# madiz_plate_sheet_v3_2.net
KiCad netlist of a schematic drawn in EasyEDA
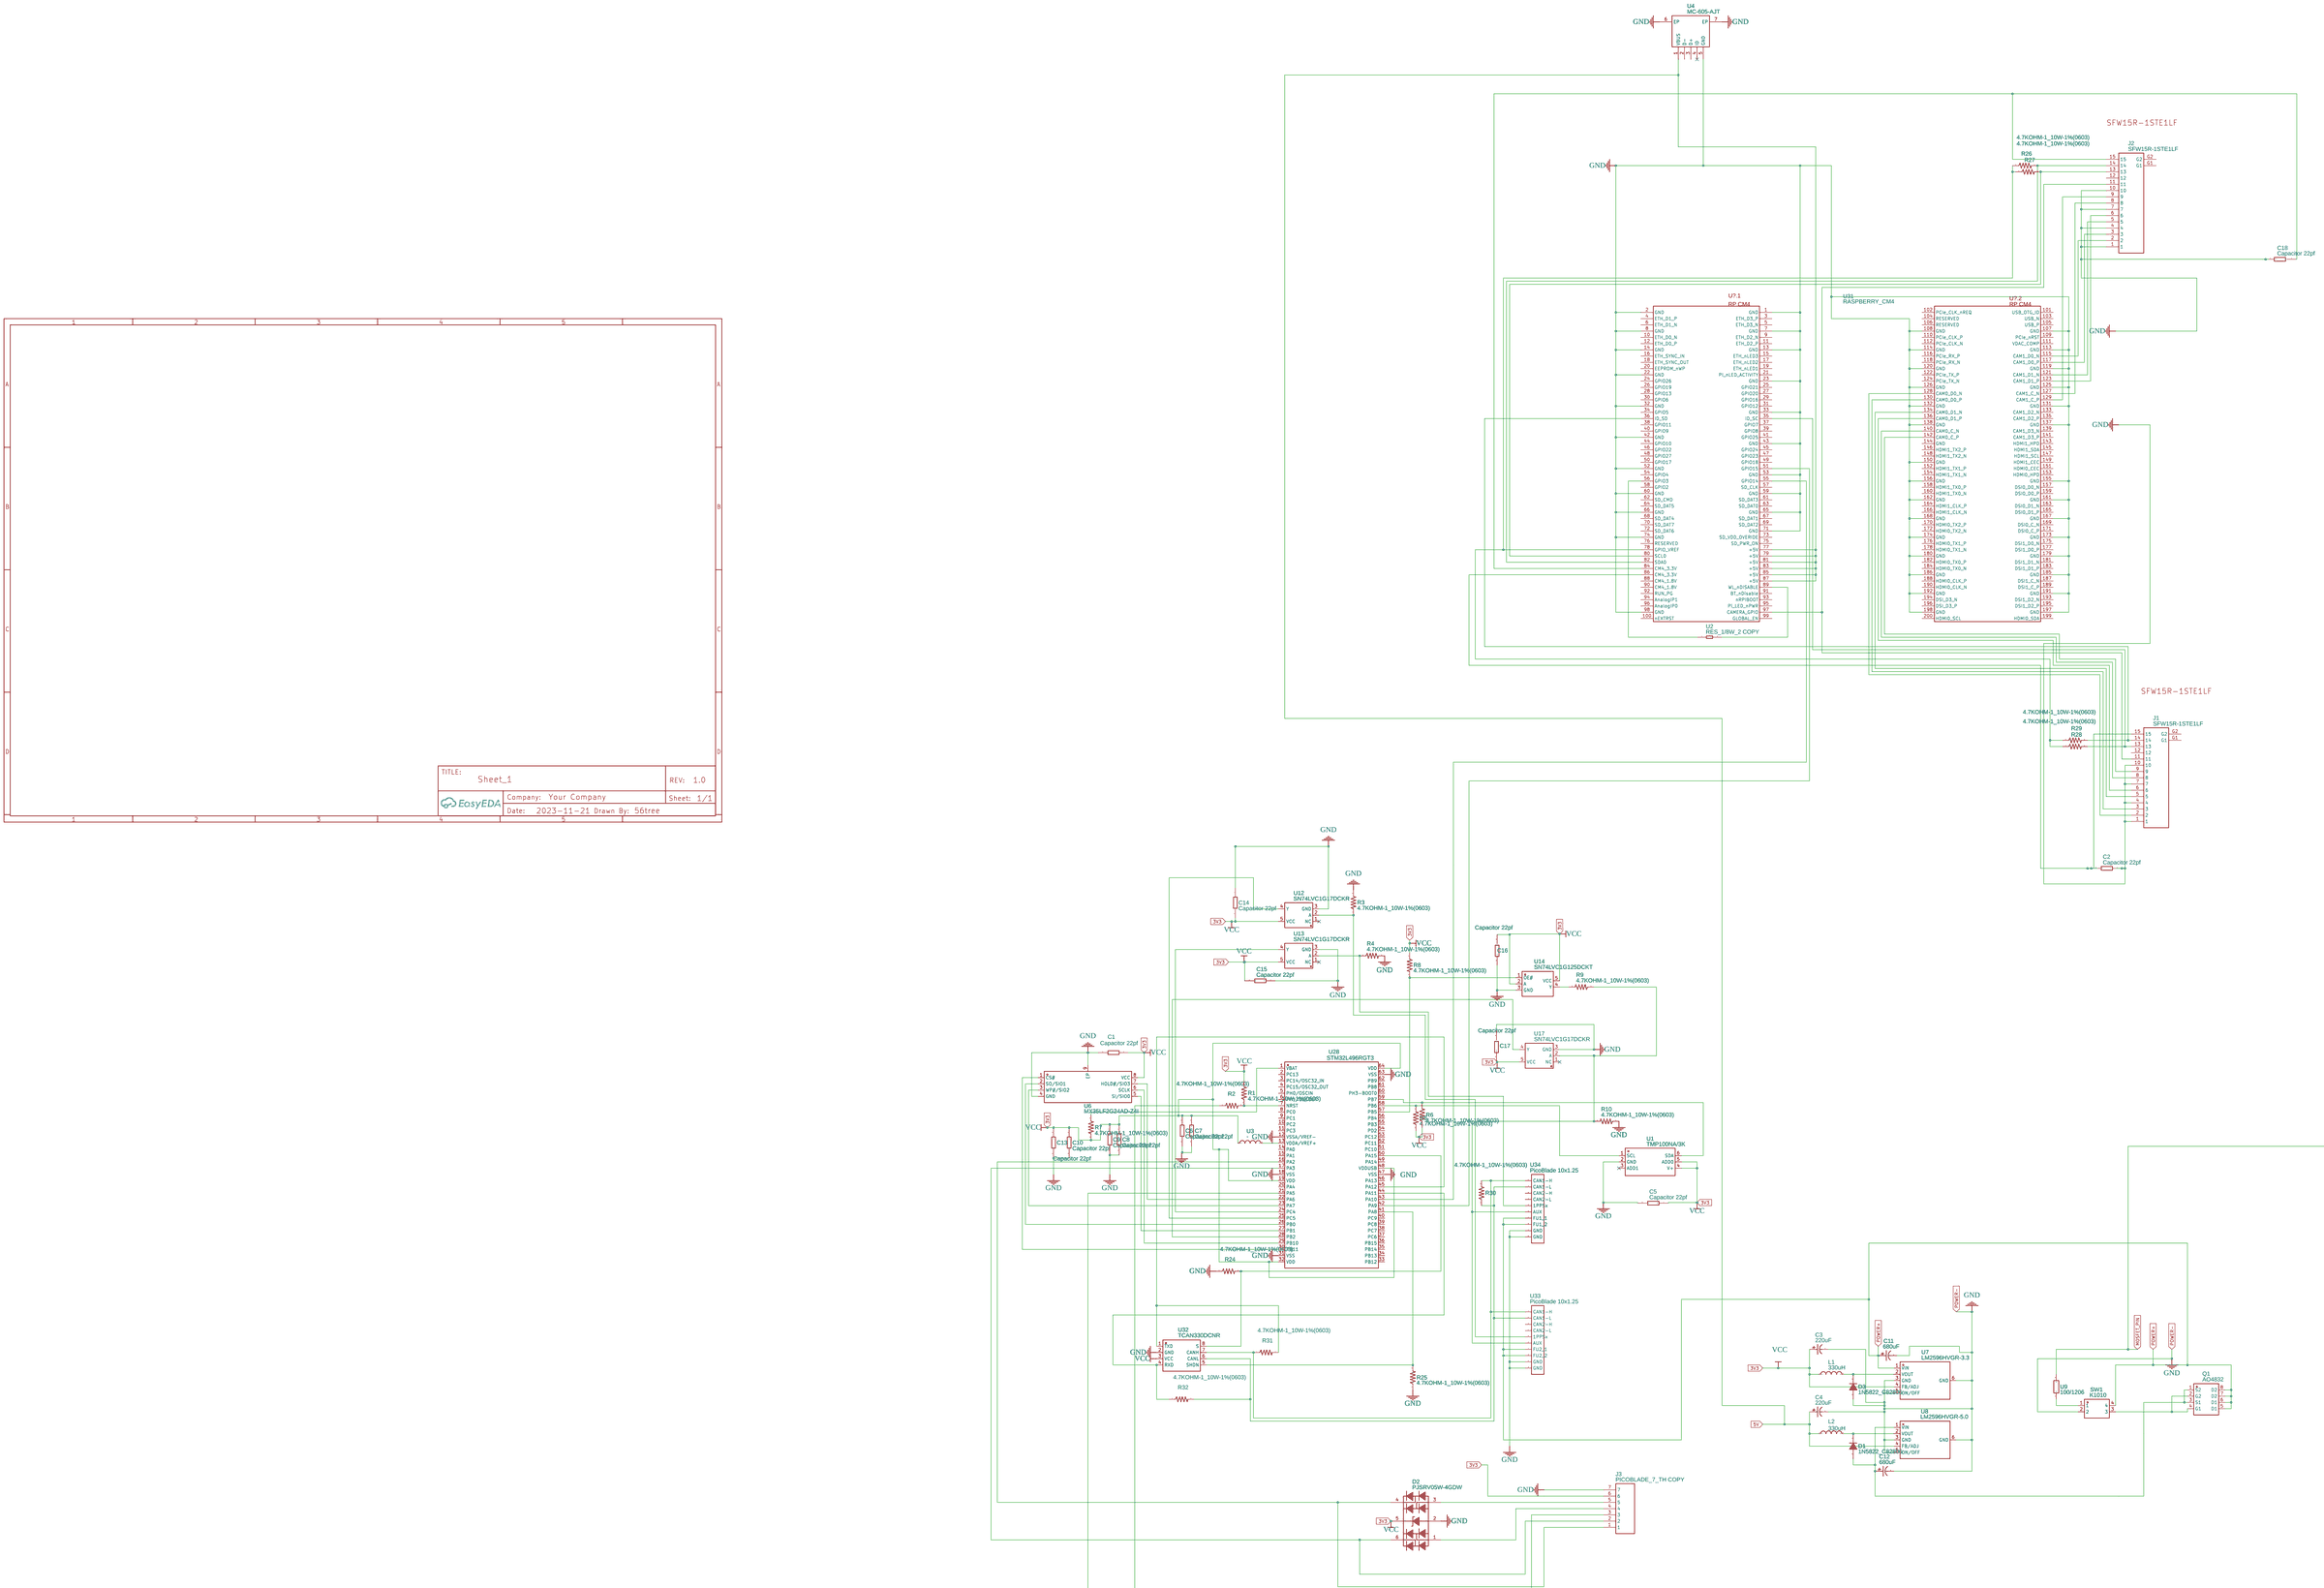
[diagram p0: schematic sheet]

(export (version "E")
  (design (tool "Eeschema 10.0.6"))
  (components
    (comp (ref "C1")
      (value "Capacitor 22pf")
      (fields (field (name "Manufacturer Part") "C0805C220J5GACTU") (field (name "Manufacturer") "KEMET"))
      (libsource (lib "") (part "Capacitor 22pf_1"))
    )
    (comp (ref "C2")
      (value "Capacitor 22pf")
      (fields (field (name "Manufacturer Part") "C0805C220J5GACTU") (field (name "Manufacturer") "KEMET"))
      (libsource (lib "") (part "Capacitor 22pf_1"))
    )
    (comp (ref "C3")
      (value "220uF")
      (fields
        (field (name "Manufacturer Part") "KS227M016F07RR0VH2FP0")
        (field (name "Manufacturer") "CX(承兴)")
      )
      (libsource (lib "") (part "220uF 16V 8*7"))
    )
    (comp (ref "C4")
      (value "220uF")
      (fields
        (field (name "Manufacturer Part") "KS227M016F07RR0VH2FP0")
        (field (name "Manufacturer") "CX(承兴)")
      )
      (libsource (lib "") (part "220uF 16V 8*7"))
    )
    (comp (ref "C5")
      (value "Capacitor 22pf")
      (fields (field (name "Manufacturer Part") "C0805C220J5GACTU") (field (name "Manufacturer") "KEMET"))
      (libsource (lib "") (part "Capacitor 22pf_1"))
    )
    (comp (ref "C6")
      (value "Capacitor 22pf")
      (fields (field (name "Manufacturer Part") "C0805C220J5GACTU") (field (name "Manufacturer") "KEMET"))
      (libsource (lib "") (part "Capacitor 22pf"))
    )
    (comp (ref "C7")
      (value "Capacitor 22pf")
      (fields (field (name "Manufacturer Part") "C0805C220J5GACTU") (field (name "Manufacturer") "KEMET"))
      (libsource (lib "") (part "Capacitor 22pf"))
    )
    (comp (ref "C8")
      (value "Capacitor 22pf")
      (fields (field (name "Manufacturer Part") "C0805C220J5GACTU") (field (name "Manufacturer") "KEMET"))
      (libsource (lib "") (part "Capacitor 22pf"))
    )
    (comp (ref "C9")
      (value "Capacitor 22pf")
      (fields (field (name "Manufacturer Part") "C0805C220J5GACTU") (field (name "Manufacturer") "KEMET"))
      (libsource (lib "") (part "Capacitor 22pf"))
    )
    (comp (ref "C10")
      (value "Capacitor 22pf")
      (fields (field (name "Manufacturer Part") "C0805C220J5GACTU") (field (name "Manufacturer") "KEMET"))
      (libsource (lib "") (part "Capacitor 22pf"))
    )
    (comp (ref "C11")
      (value "680uF")
      (fields
        (field (name "Manufacturer Part") "GR687M016F16RR0VL4FP0")
        (field (name "Manufacturer") "CX(承兴)")
      )
      (libsource (lib "") (part "680uF 16V 8*16"))
    )
    (comp (ref "C12")
      (value "680uF")
      (fields
        (field (name "Manufacturer Part") "GR687M016F16RR0VL4FP0")
        (field (name "Manufacturer") "CX(承兴)")
      )
      (libsource (lib "") (part "680uF 16V 8*16"))
    )
    (comp (ref "C13")
      (value "Capacitor 22pf")
      (fields (field (name "Manufacturer Part") "C0805C220J5GACTU") (field (name "Manufacturer") "KEMET"))
      (libsource (lib "") (part "Capacitor 22pf"))
    )
    (comp (ref "C14")
      (value "Capacitor 22pf")
      (fields (field (name "Manufacturer Part") "C0805C220J5GACTU") (field (name "Manufacturer") "KEMET"))
      (libsource (lib "") (part "Capacitor 22pf"))
    )
    (comp (ref "C15")
      (value "Capacitor 22pf")
      (fields (field (name "Manufacturer Part") "C0805C220J5GACTU") (field (name "Manufacturer") "KEMET"))
      (libsource (lib "") (part "Capacitor 22pf_1"))
    )
    (comp (ref "C16")
      (value "Capacitor 22pf")
      (fields (field (name "Manufacturer Part") "C0805C220J5GACTU") (field (name "Manufacturer") "KEMET"))
      (libsource (lib "") (part "Capacitor 22pf_3"))
    )
    (comp (ref "C17")
      (value "Capacitor 22pf")
      (fields (field (name "Manufacturer Part") "C0805C220J5GACTU") (field (name "Manufacturer") "KEMET"))
      (libsource (lib "") (part "Capacitor 22pf_3"))
    )
    (comp (ref "C18")
      (value "Capacitor 22pf")
      (fields (field (name "Manufacturer Part") "C0805C220J5GACTU") (field (name "Manufacturer") "KEMET"))
      (libsource (lib "") (part "Capacitor 22pf_2"))
    )
    (comp (ref "D1")
      (value "1N5822_C82806")
      (fields (field (name "Manufacturer Part") "1N5822") (field (name "Manufacturer") "LRC(乐山无线电)"))
      (libsource (lib "") (part "1N5822_C82806"))
    )
    (comp (ref "D2")
      (value "PJSRV05W-4GDW")
      (fields
        (field (name "Manufacturer Part") "PJSRV05W-4GDW_R1_00001")
        (field (name "Manufacturer") "PANJIT(强茂)")
      )
      (libsource (lib "") (part "PJSRV05W-4GDW"))
    )
    (comp (ref "D3")
      (value "1N5822_C82806")
      (fields (field (name "Manufacturer Part") "1N5822") (field (name "Manufacturer") "LRC(乐山无线电)"))
      (libsource (lib "") (part "1N5822_C82806"))
    )
    (comp (ref "J1")
      (value "SFW15R-1STE1LF")
      (fields (field (name "Manufacturer") "Amphenol FCI"))
      (libsource (lib "") (part "SFW15R-1STE1LF_1"))
    )
    (comp (ref "J2")
      (value "SFW15R-1STE1LF")
      (fields (field (name "Manufacturer") "Amphenol FCI"))
      (libsource (lib "") (part "SFW15R-1STE1LF"))
    )
    (comp (ref "J3")
      (value "PICOBLADE_7_TH COPY")
      (fields (field (name "Manufacturer Part") "0530481510"))
      (libsource (lib "") (part "PICOBLADE_7_TH COPY"))
    )
    (comp (ref "L1")
      (value "330uH")
      (fields (field (name "Manufacturer Part") "B82477G4334M000") (field (name "Manufacturer") "TDK"))
      (libsource (lib "") (part "B82477G4334M000"))
    )
    (comp (ref "L2")
      (value "330uH")
      (fields (field (name "Manufacturer Part") "B82477G4334M000") (field (name "Manufacturer") "TDK"))
      (libsource (lib "") (part "B82477G4334M000"))
    )
    (comp (ref "Q1")
      (value "AO4832")
      (fields (field (name "Manufacturer") "AOS"))
      (libsource (lib "") (part "AO4832"))
    )
    (comp (ref "R1") (value "4.7KOHM-1_10W-1%(0603)") (libsource (lib "") (part "4.7KOHM-1_10W-1%(0603)_2")))
    (comp (ref "R2") (value "4.7KOHM-1_10W-1%(0603)") (libsource (lib "") (part "4.7KOHM-1_10W-1%(0603)")))
    (comp (ref "R3") (value "4.7KOHM-1_10W-1%(0603)") (libsource (lib "") (part "4.7KOHM-1_10W-1%(0603)_2")))
    (comp (ref "R4") (value "4.7KOHM-1_10W-1%(0603)") (libsource (lib "") (part "4.7KOHM-1_10W-1%(0603)")))
    (comp (ref "R5") (value "4.7KOHM-1_10W-1%(0603)") (libsource (lib "") (part "4.7KOHM-1_10W-1%(0603)_2")))
    (comp (ref "R6") (value "4.7KOHM-1_10W-1%(0603)") (libsource (lib "") (part "4.7KOHM-1_10W-1%(0603)_2")))
    (comp (ref "R7") (value "4.7KOHM-1_10W-1%(0603)") (libsource (lib "") (part "4.7KOHM-1_10W-1%(0603)_2")))
    (comp (ref "R8") (value "4.7KOHM-1_10W-1%(0603)") (libsource (lib "") (part "4.7KOHM-1_10W-1%(0603)_3")))
    (comp (ref "R9") (value "4.7KOHM-1_10W-1%(0603)") (libsource (lib "") (part "4.7KOHM-1_10W-1%(0603)_1")))
    (comp (ref "R10") (value "4.7KOHM-1_10W-1%(0603)") (libsource (lib "") (part "4.7KOHM-1_10W-1%(0603)_1")))
    (comp (ref "R24") (value "4.7KOHM-1_10W-1%(0603)") (libsource (lib "") (part "4.7KOHM-1_10W-1%(0603)")))
    (comp (ref "R25") (value "4.7KOHM-1_10W-1%(0603)") (libsource (lib "") (part "4.7KOHM-1_10W-1%(0603)_2")))
    (comp (ref "R26") (value "4.7KOHM-1_10W-1%(0603)") (libsource (lib "") (part "4.7KOHM-1_10W-1%(0603)")))
    (comp (ref "R27") (value "4.7KOHM-1_10W-1%(0603)") (libsource (lib "") (part "4.7KOHM-1_10W-1%(0603)")))
    (comp (ref "R28") (value "4.7KOHM-1_10W-1%(0603)") (libsource (lib "") (part "4.7KOHM-1_10W-1%(0603)")))
    (comp (ref "R29") (value "4.7KOHM-1_10W-1%(0603)") (libsource (lib "") (part "4.7KOHM-1_10W-1%(0603)")))
    (comp (ref "R30") (value "4.7KOHM-1_10W-1%(0603)") (libsource (lib "") (part "4.7KOHM-1_10W-1%(0603)_2")))
    (comp (ref "R31") (value "4.7KOHM-1_10W-1%(0603)") (libsource (lib "") (part "4.7KOHM-1_10W-1%(0603)")))
    (comp (ref "R32") (value "4.7KOHM-1_10W-1%(0603)") (libsource (lib "") (part "4.7KOHM-1_10W-1%(0603)")))
    (comp (ref "SW1")
      (value "K1010")
      (fields (field (name "Manufacturer") "Cosmo"))
      (libsource (lib "") (part "K1010"))
    )
    (comp (ref "U1")
      (value "TMP100NA/3K")
      (fields (field (name "Manufacturer") "TI(德州仪器)"))
      (libsource (lib "") (part "TMP100NA/3K"))
    )
    (comp (ref "U2") (value "RES_1/8W_2 COPY") (libsource (lib "") (part "RES_1/8W_2 COPY")))
    (comp (ref "U3")
      (value "-")
      (fields (field (name "Manufacturer Part") "SDR0302-151KL"))
      (libsource (lib "") (part "SDR0302-151KL"))
    )
    (comp (ref "U4")
      (value "MC-605-AJT")
      (fields (field (name "Manufacturer") "HANBO(汉博)"))
      (libsource (lib "") (part "MC-605-AJT"))
    )
    (comp (ref "U6")
      (value "MX35LF2G24AD-Z4I")
      (fields (field (name "Manufacturer") "MXIC(旺宏电子)"))
      (libsource (lib "") (part "MX35LF2G24AD-Z4I"))
    )
    (comp (ref "U7")
      (value "LM2596HVGR-3.3")
      (fields (field (name "Manufacturer Part") "LM2596HVGR-5.0") (field (name "Manufacturer") "HTC"))
      (libsource (lib "") (part "LM2596HVGR-5.0"))
    )
    (comp (ref "U8")
      (value "LM2596HVGR-5.0")
      (fields (field (name "Manufacturer") "HTC"))
      (libsource (lib "") (part "LM2596HVGR-5.0"))
    )
    (comp (ref "U9")
      (value "100/1206")
      (fields (field (name "Manufacturer Part") "1K2/1206"))
      (libsource (lib "") (part "1K2/1206"))
    )
    (comp (ref "U12")
      (value "SN74LVC1G17DCKR")
      (fields (field (name "Manufacturer") "TI(德州仪器)"))
      (libsource (lib "") (part "SN74LVC1G17DCKR"))
    )
    (comp (ref "U13")
      (value "SN74LVC1G17DCKR")
      (fields (field (name "Manufacturer") "TI(德州仪器)"))
      (libsource (lib "") (part "SN74LVC1G17DCKR"))
    )
    (comp (ref "U14")
      (value "SN74LVC1G125DCKT")
      (fields (field (name "Manufacturer") "TI(德州仪器)"))
      (libsource (lib "") (part "SN74LVC1G125DCKT"))
    )
    (comp (ref "U17")
      (value "SN74LVC1G17DCKR")
      (fields (field (name "Manufacturer") "TI(德州仪器)"))
      (libsource (lib "") (part "SN74LVC1G17DCKR"))
    )
    (comp (ref "U28")
      (value "STM32L496RGT3")
      (fields (field (name "Manufacturer") "ST(意法半导体)"))
      (libsource (lib "") (part "STM32L496RGT3"))
    )
    (comp (ref "U31") (value "RASPBERRY_CM4") (libsource (lib "") (part "RASPBERRY_CM4")))
    (comp (ref "U32")
      (value "TCAN330DCNR")
      (fields (field (name "Manufacturer") "TI(德州仪器)"))
      (libsource (lib "") (part "TCAN330DCNR"))
    )
    (comp (ref "U33")
      (value "PicoBlade 10x1.25")
      (fields (field (name "Manufacturer Part") "15134-1002") (field (name "Manufacturer") "Molex"))
      (libsource (lib "") (part "PicoBlade 10x1.25_1"))
    )
    (comp (ref "U34")
      (value "PicoBlade 10x1.25")
      (fields (field (name "Manufacturer Part") "15134-1002") (field (name "Manufacturer") "Molex"))
      (libsource (lib "") (part "PicoBlade 10x1.25"))
    )
  )
  (nets
    (net (code "1") (name "3V3") (class "Default")
      (node (ref "C1") (pin "1") (pinfunction "1_1") (pintype "unspecified"))
      (node (ref "C10") (pin "1") (pinfunction "1_1") (pintype "unspecified"))
      (node (ref "C13") (pin "1") (pinfunction "1_1") (pintype "unspecified"))
      (node (ref "C14") (pin "2") (pinfunction "2_2") (pintype "unspecified"))
      (node (ref "C15") (pin "2") (pinfunction "2_2") (pintype "unspecified"))
      (node (ref "C16") (pin "2") (pinfunction "2_2") (pintype "unspecified"))
      (node (ref "C17") (pin "1") (pinfunction "1_1") (pintype "unspecified"))
      (node (ref "C3") (pin "1") (pinfunction "1_1") (pintype "input"))
      (node (ref "C5") (pin "1") (pinfunction "1_1") (pintype "unspecified"))
      (node (ref "C6") (pin "1") (pinfunction "1_1") (pintype "unspecified"))
      (node (ref "C7") (pin "1") (pinfunction "1_1") (pintype "unspecified"))
      (node (ref "C8") (pin "1") (pinfunction "1_1") (pintype "unspecified"))
      (node (ref "C9") (pin "1") (pinfunction "1_1") (pintype "unspecified"))
      (node (ref "D2") (pin "5") (pinfunction "5_5") (pintype "unspecified"))
      (node (ref "J3") (pin "6") (pinfunction "6_6") (pintype "unspecified"))
      (node (ref "L1") (pin "1") (pinfunction "1_1") (pintype "unspecified"))
      (node (ref "R1") (pin "2") (pinfunction "2_2") (pintype "unspecified"))
      (node (ref "R5") (pin "1") (pinfunction "1_1") (pintype "unspecified"))
      (node (ref "R6") (pin "1") (pinfunction "1_1") (pintype "unspecified"))
      (node (ref "R7") (pin "1") (pinfunction "1_1") (pintype "unspecified"))
      (node (ref "R8") (pin "1") (pinfunction "1_1") (pintype "unspecified"))
      (node (ref "U1") (pin "4") (pinfunction "V+_4") (pintype "unspecified"))
      (node (ref "U1") (pin "5") (pinfunction "ADD0_5") (pintype "unspecified"))
      (node (ref "U12") (pin "5") (pinfunction "VCC_5") (pintype "unspecified"))
      (node (ref "U13") (pin "5") (pinfunction "VCC_5") (pintype "unspecified"))
      (node (ref "U14") (pin "2") (pinfunction "A_2") (pintype "unspecified"))
      (node (ref "U14") (pin "5") (pinfunction "VCC_5") (pintype "unspecified"))
      (node (ref "U17") (pin "5") (pinfunction "VCC_5") (pintype "unspecified"))
      (node (ref "U28") (pin "19") (pinfunction "VDD_19") (pintype "unspecified"))
      (node (ref "U28") (pin "32") (pinfunction "VDD_32") (pintype "unspecified"))
      (node (ref "U28") (pin "48") (pinfunction "VDDUSB_48") (pintype "unspecified"))
      (node (ref "U28") (pin "64") (pinfunction "VDD_64") (pintype "unspecified"))
      (node (ref "U3") (pin "1") (pinfunction "1_1") (pintype "unspecified"))
      (node (ref "U32") (pin "3") (pinfunction "VCC_3") (pintype "unspecified"))
      (node (ref "U6") (pin "8") (pinfunction "VCC_8") (pintype "unspecified"))
      (node (ref "U7") (pin "4") (pinfunction "FB/ADJ_4") (pintype "unspecified"))
    )
    (net (code "2") (name "5V") (class "Default")
      (node (ref "C4") (pin "1") (pinfunction "1_1") (pintype "input"))
      (node (ref "L2") (pin "1") (pinfunction "1_1") (pintype "unspecified"))
      (node (ref "U31") (pin "77") (pinfunction "+5V_77") (pintype "bidirectional"))
      (node (ref "U31") (pin "79") (pinfunction "+5V_79") (pintype "bidirectional"))
      (node (ref "U31") (pin "81") (pinfunction "+5V_81") (pintype "bidirectional"))
      (node (ref "U31") (pin "83") (pinfunction "+5V_83") (pintype "bidirectional"))
      (node (ref "U31") (pin "85") (pinfunction "+5V_85") (pintype "bidirectional"))
      (node (ref "U31") (pin "87") (pinfunction "+5V_87") (pintype "bidirectional"))
      (node (ref "U4") (pin "1") (pinfunction "VBUS_1") (pintype "unspecified"))
      (node (ref "U8") (pin "4") (pinfunction "FB/ADJ_4") (pintype "unspecified"))
    )
    (net (code "3") (name "MOSFET_PIN") (class "Default")
      (node (ref "U28") (pin "21") (pinfunction "PA5_21") (pintype "unspecified"))
      (node (ref "U9") (pin "2") (pinfunction "2_2") (pintype "unspecified"))
    )
    (net (code "4") (name "Net-(C2-Pad2)") (class "Default")
      (node (ref "C2") (pin "2") (pinfunction "2_2") (pintype "unspecified"))
      (node (ref "J1") (pin "15") (pinfunction "15_15") (pintype "unspecified"))
      (node (ref "U31") (pin "86") (pinfunction "CM4_3.3V_86") (pintype "bidirectional"))
    )
    (net (code "5") (name "Net-(C18-Pad2)") (class "Default")
      (node (ref "C18") (pin "2") (pinfunction "2_2") (pintype "unspecified"))
      (node (ref "J2") (pin "15") (pinfunction "15_15") (pintype "unspecified"))
      (node (ref "U31") (pin "84") (pinfunction "CM4_3.3V_84") (pintype "bidirectional"))
    )
    (net (code "6") (name "Net-(D1-A)") (class "Default")
      (node (ref "C12") (pin "1") (pinfunction "1_1") (pintype "input"))
      (node (ref "D1") (pin "2") (pinfunction "A_2") (pintype "unspecified"))
      (node (ref "Q1") (pin "1") (pinfunction "S2_1") (pintype "unspecified"))
      (node (ref "Q1") (pin "3") (pinfunction "S1_3") (pintype "unspecified"))
      (node (ref "U8") (pin "1") (pinfunction "VIN_1") (pintype "unspecified"))
    )
    (net (code "7") (name "Net-(D1-C)") (class "Default")
      (node (ref "D1") (pin "1") (pinfunction "C_1") (pintype "unspecified"))
      (node (ref "L2") (pin "2") (pinfunction "2_2") (pintype "unspecified"))
      (node (ref "U8") (pin "2") (pinfunction "VOUT_2") (pintype "unspecified"))
    )
    (net (code "8") (name "Net-(D2-Pad1)") (class "Default")
      (node (ref "D2") (pin "1") (pinfunction "1_1") (pintype "unspecified"))
      (node (ref "J3") (pin "4") (pinfunction "4_4") (pintype "unspecified"))
    )
    (net (code "9") (name "Net-(D2-Pad3)") (class "Default")
      (node (ref "D2") (pin "3") (pinfunction "3_3") (pintype "unspecified"))
      (node (ref "J3") (pin "5") (pinfunction "5_5") (pintype "unspecified"))
    )
    (net (code "10") (name "Net-(D3-C)") (class "Default")
      (node (ref "D3") (pin "1") (pinfunction "C_1") (pintype "unspecified"))
      (node (ref "L1") (pin "2") (pinfunction "2_2") (pintype "unspecified"))
      (node (ref "U7") (pin "2") (pinfunction "VOUT_2") (pintype "unspecified"))
    )
    (net (code "11") (name "Net-(J3-Pad3)") (class "Default")
      (node (ref "J3") (pin "3") (pinfunction "3_3") (pintype "unspecified"))
      (node (ref "R2") (pin "1") (pinfunction "1_1") (pintype "unspecified"))
    )
    (net (code "12") (name "Net-(Q1-G1)") (class "Default")
      (node (ref "Q1") (pin "2") (pinfunction "G2_2") (pintype "unspecified"))
      (node (ref "Q1") (pin "4") (pinfunction "G1_4") (pintype "unspecified"))
      (node (ref "SW1") (pin "3") (pinfunction "3_3") (pintype "unspecified"))
    )
    (net (code "13") (name "Net-(SW1-Pad1)") (class "Default")
      (node (ref "SW1") (pin "1") (pinfunction "1_1") (pintype "unspecified"))
      (node (ref "U9") (pin "1") (pinfunction "1_1") (pintype "unspecified"))
    )
    (net (code "14") (name "Net-(U1-SCL)") (class "Default")
      (node (ref "R5") (pin "2") (pinfunction "2_2") (pintype "unspecified"))
      (node (ref "U1") (pin "1") (pinfunction "SCL_1") (pintype "unspecified"))
      (node (ref "U28") (pin "58") (pinfunction "PB6_58") (pintype "unspecified"))
    )
    (net (code "15") (name "Net-(U1-SDA)") (class "Default")
      (node (ref "R6") (pin "2") (pinfunction "2_2") (pintype "unspecified"))
      (node (ref "U1") (pin "6") (pinfunction "SDA_6") (pintype "unspecified"))
      (node (ref "U28") (pin "59") (pinfunction "PB7_59") (pintype "unspecified"))
    )
    (net (code "16") (name "Net-(U12-A)") (class "Default")
      (node (ref "R3") (pin "1") (pinfunction "1_1") (pintype "unspecified"))
      (node (ref "U12") (pin "2") (pinfunction "A_2") (pintype "unspecified"))
      (node (ref "U33") (pin "5") (pinfunction "1PPSx_5") (pintype "unspecified"))
    )
    (net (code "17") (name "Net-(U12-Y)") (class "Default")
      (node (ref "U12") (pin "4") (pinfunction "Y_4") (pintype "unspecified"))
      (node (ref "U28") (pin "25") (pinfunction "PC5_25") (pintype "unspecified"))
    )
    (net (code "18") (name "Net-(U13-A)") (class "Default")
      (node (ref "R4") (pin "1") (pinfunction "1_1") (pintype "unspecified"))
      (node (ref "U13") (pin "2") (pinfunction "A_2") (pintype "unspecified"))
      (node (ref "U34") (pin "5") (pinfunction "1PPSx_5") (pintype "unspecified"))
    )
    (net (code "19") (name "Net-(U13-Y)") (class "Default")
      (node (ref "U13") (pin "4") (pinfunction "Y_4") (pintype "unspecified"))
      (node (ref "U28") (pin "24") (pinfunction "PC4_24") (pintype "unspecified"))
    )
    (net (code "20") (name "Net-(U14-OE#)") (class "Default")
      (node (ref "R8") (pin "2") (pinfunction "2_2") (pintype "unspecified"))
      (node (ref "U14") (pin "1") (pinfunction "OE#_1") (pintype "unspecified"))
      (node (ref "U28") (pin "57") (pinfunction "PB5_57") (pintype "unspecified"))
    )
    (net (code "21") (name "Net-(U14-Y)") (class "Default")
      (node (ref "R9") (pin "2") (pinfunction "2_2") (pintype "unspecified"))
      (node (ref "U14") (pin "4") (pinfunction "Y_4") (pintype "unspecified"))
    )
    (net (code "22") (name "Net-(U17-A)") (class "Default")
      (node (ref "R10") (pin "2") (pinfunction "2_2") (pintype "unspecified"))
      (node (ref "R9") (pin "1") (pinfunction "1_1") (pintype "unspecified"))
      (node (ref "U17") (pin "2") (pinfunction "A_2") (pintype "unspecified"))
      (node (ref "U33") (pin "6") (pinfunction "AUX_6") (pintype "unspecified"))
      (node (ref "U34") (pin "6") (pinfunction "AUX_6") (pintype "unspecified"))
    )
    (net (code "23") (name "Net-(U17-Y)") (class "Default")
      (node (ref "U17") (pin "4") (pinfunction "Y_4") (pintype "unspecified"))
      (node (ref "U28") (pin "28") (pinfunction "PB2_28") (pintype "unspecified"))
    )
    (net (code "24") (name "Net-(U28-NRST)") (class "Default")
      (node (ref "R1") (pin "1") (pinfunction "1_1") (pintype "unspecified"))
      (node (ref "R2") (pin "2") (pinfunction "2_2") (pintype "unspecified"))
      (node (ref "U28") (pin "7") (pinfunction "NRST_7") (pintype "unspecified"))
    )
    (net (code "25") (name "Net-(U28-PA2)") (class "Default")
      (node (ref "D2") (pin "4") (pinfunction "4_4") (pintype "unspecified"))
      (node (ref "J3") (pin "1") (pinfunction "1_1") (pintype "unspecified"))
      (node (ref "U28") (pin "16") (pinfunction "PA2_16") (pintype "unspecified"))
    )
    (net (code "26") (name "Net-(U28-PA3)") (class "Default")
      (node (ref "D2") (pin "6") (pinfunction "6_6") (pintype "unspecified"))
      (node (ref "J3") (pin "2") (pinfunction "2_2") (pintype "unspecified"))
      (node (ref "U28") (pin "17") (pinfunction "PA3_17") (pintype "unspecified"))
    )
    (net (code "27") (name "Net-(U28-PA6)") (class "Default")
      (node (ref "U28") (pin "22") (pinfunction "PA6_22") (pintype "unspecified"))
      (node (ref "U6") (pin "7") (pinfunction "HOLD#/SIO3_7") (pintype "unspecified"))
    )
    (net (code "28") (name "Net-(U28-PA7)") (class "Default")
      (node (ref "U28") (pin "23") (pinfunction "PA7_23") (pintype "unspecified"))
      (node (ref "U6") (pin "3") (pinfunction "WP#/SIO2_3") (pintype "unspecified"))
    )
    (net (code "29") (name "Net-(U28-PA8)") (class "Default")
      (node (ref "R25") (pin "2") (pinfunction "2_2") (pintype "unspecified"))
      (node (ref "U28") (pin "41") (pinfunction "PA8_41") (pintype "unspecified"))
      (node (ref "U32") (pin "5") (pinfunction "SHDN_5") (pintype "unspecified"))
    )
    (net (code "30") (name "Net-(U28-PA9)") (class "Default")
      (node (ref "U28") (pin "42") (pinfunction "PA9_42") (pintype "unspecified"))
      (node (ref "U31") (pin "51") (pinfunction "GPIO15_51") (pintype "bidirectional"))
    )
    (net (code "31") (name "Net-(U28-PA10)") (class "Default")
      (node (ref "U28") (pin "43") (pinfunction "PA10_43") (pintype "unspecified"))
      (node (ref "U31") (pin "55") (pinfunction "GPIO14_55") (pintype "bidirectional"))
    )
    (net (code "32") (name "Net-(U28-PA11)") (class "Default")
      (node (ref "R32") (pin "1") (pinfunction "1_1") (pintype "unspecified"))
      (node (ref "U28") (pin "44") (pinfunction "PA11_44") (pintype "unspecified"))
      (node (ref "U32") (pin "4") (pinfunction "RXD_4") (pintype "unspecified"))
    )
    (net (code "33") (name "Net-(U28-PA12)") (class "Default")
      (node (ref "R31") (pin "2") (pinfunction "2_2") (pintype "unspecified"))
      (node (ref "U28") (pin "45") (pinfunction "PA12_45") (pintype "unspecified"))
      (node (ref "U32") (pin "1") (pinfunction "TXD_1") (pintype "unspecified"))
    )
    (net (code "34") (name "Net-(U28-PA15)") (class "Default")
      (node (ref "R24") (pin "2") (pinfunction "2_2") (pintype "unspecified"))
      (node (ref "U28") (pin "50") (pinfunction "PA15_50") (pintype "unspecified"))
      (node (ref "U32") (pin "8") (pinfunction "S_8") (pintype "unspecified"))
    )
    (net (code "35") (name "Net-(U28-PB0)") (class "Default")
      (node (ref "U28") (pin "26") (pinfunction "PB0_26") (pintype "unspecified"))
      (node (ref "U6") (pin "2") (pinfunction "SO/SIO1_2") (pintype "unspecified"))
    )
    (net (code "36") (name "Net-(U28-PB1)") (class "Default")
      (node (ref "U28") (pin "27") (pinfunction "PB1_27") (pintype "unspecified"))
      (node (ref "U6") (pin "5") (pinfunction "SI/SIO0_5") (pintype "unspecified"))
    )
    (net (code "37") (name "Net-(U28-PB10)") (class "Default")
      (node (ref "U28") (pin "29") (pinfunction "PB10_29") (pintype "unspecified"))
      (node (ref "U6") (pin "6") (pinfunction "SCLK_6") (pintype "unspecified"))
    )
    (net (code "38") (name "Net-(U28-PB11)") (class "Default")
      (node (ref "U28") (pin "30") (pinfunction "PB11_30") (pintype "unspecified"))
      (node (ref "U6") (pin "1") (pinfunction "CS#_1") (pintype "unspecified"))
    )
    (net (code "39") (name "Net-(U28-VBAT)") (class "Default")
      (node (ref "R7") (pin "2") (pinfunction "2_2") (pintype "unspecified"))
      (node (ref "U28") (pin "1") (pinfunction "VBAT_1") (pintype "unspecified"))
    )
    (net (code "40") (name "Net-(U28-VDDA{slash}VREF+)") (class "Default")
      (node (ref "U28") (pin "13") (pinfunction "VDDA/VREF+_13") (pintype "unspecified"))
      (node (ref "U3") (pin "2") (pinfunction "2_2") (pintype "unspecified"))
    )
    (net (code "41") (name "Net-(U31-CAM0_C_N)") (class "Default")
      (node (ref "J1") (pin "8") (pinfunction "8_8") (pintype "unspecified"))
      (node (ref "U31") (pin "140") (pinfunction "CAM0_C_N_140") (pintype "bidirectional"))
    )
    (net (code "42") (name "Net-(U31-CAM0_C_P)") (class "Default")
      (node (ref "J1") (pin "9") (pinfunction "9_9") (pintype "unspecified"))
      (node (ref "U31") (pin "142") (pinfunction "CAM0_C_P_142") (pintype "bidirectional"))
    )
    (net (code "43") (name "Net-(U31-CAM0_D0_N)") (class "Default")
      (node (ref "J1") (pin "2") (pinfunction "2_2") (pintype "unspecified"))
      (node (ref "U31") (pin "128") (pinfunction "CAM0_D0_N_128") (pintype "bidirectional"))
    )
    (net (code "44") (name "Net-(U31-CAM0_D0_P)") (class "Default")
      (node (ref "J1") (pin "3") (pinfunction "3_3") (pintype "unspecified"))
      (node (ref "U31") (pin "130") (pinfunction "CAM0_D0_P_130") (pintype "bidirectional"))
    )
    (net (code "45") (name "Net-(U31-CAM0_D1_N)") (class "Default")
      (node (ref "J1") (pin "5") (pinfunction "5_5") (pintype "unspecified"))
      (node (ref "U31") (pin "134") (pinfunction "CAM0_D1_N_134") (pintype "bidirectional"))
    )
    (net (code "46") (name "Net-(U31-CAM0_D1_P)") (class "Default")
      (node (ref "J1") (pin "6") (pinfunction "6_6") (pintype "unspecified"))
      (node (ref "U31") (pin "136") (pinfunction "CAM0_D1_P_136") (pintype "bidirectional"))
    )
    (net (code "47") (name "Net-(U31-CAM1_C_N)") (class "Default")
      (node (ref "J2") (pin "8") (pinfunction "8_8") (pintype "unspecified"))
      (node (ref "U31") (pin "127") (pinfunction "CAM1_C_N_127") (pintype "bidirectional"))
    )
    (net (code "48") (name "Net-(U31-CAM1_C_P)") (class "Default")
      (node (ref "J2") (pin "9") (pinfunction "9_9") (pintype "unspecified"))
      (node (ref "U31") (pin "129") (pinfunction "CAM1_C_P_129") (pintype "bidirectional"))
    )
    (net (code "49") (name "Net-(U31-CAM1_D0_N)") (class "Default")
      (node (ref "J2") (pin "2") (pinfunction "2_2") (pintype "unspecified"))
      (node (ref "U31") (pin "115") (pinfunction "CAM1_D0_N_115") (pintype "bidirectional"))
    )
    (net (code "50") (name "Net-(U31-CAM1_D0_P)") (class "Default")
      (node (ref "J2") (pin "3") (pinfunction "3_3") (pintype "unspecified"))
      (node (ref "U31") (pin "117") (pinfunction "CAM1_D0_P_117") (pintype "bidirectional"))
    )
    (net (code "51") (name "Net-(U31-CAM1_D1_N)") (class "Default")
      (node (ref "J2") (pin "5") (pinfunction "5_5") (pintype "unspecified"))
      (node (ref "U31") (pin "121") (pinfunction "CAM1_D1_N_121") (pintype "bidirectional"))
    )
    (net (code "52") (name "Net-(U31-CAM1_D1_P)") (class "Default")
      (node (ref "J2") (pin "6") (pinfunction "6_6") (pintype "unspecified"))
      (node (ref "U31") (pin "123") (pinfunction "CAM1_D1_P_123") (pintype "bidirectional"))
    )
    (net (code "53") (name "Net-(U31-CAMERA_GPIO)") (class "Default")
      (node (ref "J1") (pin "11") (pinfunction "11_11") (pintype "unspecified"))
      (node (ref "J2") (pin "11") (pinfunction "11_11") (pintype "unspecified"))
      (node (ref "U31") (pin "97") (pinfunction "CAMERA_GPIO_97") (pintype "bidirectional"))
    )
    (net (code "54") (name "Net-(U31-GPIO3)") (class "Default")
      (node (ref "U2") (pin "1") (pinfunction "1_1") (pintype "unspecified"))
      (node (ref "U31") (pin "56") (pinfunction "GPIO3_56") (pintype "bidirectional"))
    )
    (net (code "55") (name "Net-(U31-GPIO_VREF)") (class "Default")
      (node (ref "R26") (pin "1") (pinfunction "1_1") (pintype "unspecified"))
      (node (ref "R27") (pin "1") (pinfunction "1_1") (pintype "unspecified"))
      (node (ref "R28") (pin "1") (pinfunction "1_1") (pintype "unspecified"))
      (node (ref "R29") (pin "1") (pinfunction "1_1") (pintype "unspecified"))
      (node (ref "U31") (pin "78") (pinfunction "GPIO_VREF_78") (pintype "bidirectional"))
    )
    (net (code "56") (name "Net-(U31-ID_SC)") (class "Default")
      (node (ref "J1") (pin "13") (pinfunction "13_13") (pintype "unspecified"))
      (node (ref "R28") (pin "2") (pinfunction "2_2") (pintype "unspecified"))
      (node (ref "U31") (pin "35") (pinfunction "ID_SC_35") (pintype "bidirectional"))
    )
    (net (code "57") (name "Net-(U31-ID_SD)") (class "Default")
      (node (ref "J1") (pin "14") (pinfunction "14_14") (pintype "unspecified"))
      (node (ref "R29") (pin "2") (pinfunction "2_2") (pintype "unspecified"))
      (node (ref "U31") (pin "36") (pinfunction "ID_SD_36") (pintype "bidirectional"))
    )
    (net (code "58") (name "Net-(U31-SCL0)") (class "Default")
      (node (ref "J2") (pin "13") (pinfunction "13_13") (pintype "unspecified"))
      (node (ref "R27") (pin "2") (pinfunction "2_2") (pintype "unspecified"))
      (node (ref "U31") (pin "80") (pinfunction "SCL0_80") (pintype "bidirectional"))
    )
    (net (code "59") (name "Net-(U31-SDA0)") (class "Default")
      (node (ref "J2") (pin "14") (pinfunction "14_14") (pintype "unspecified"))
      (node (ref "R26") (pin "2") (pinfunction "2_2") (pintype "unspecified"))
      (node (ref "U31") (pin "82") (pinfunction "SDA0_82") (pintype "bidirectional"))
    )
    (net (code "60") (name "Net-(U31-WL_nDISABLE)") (class "Default")
      (node (ref "U2") (pin "2") (pinfunction "2_2") (pintype "unspecified"))
      (node (ref "U31") (pin "89") (pinfunction "WL_nDISABLE_89") (pintype "bidirectional"))
    )
    (net (code "61") (name "Net-(U32-CANH)") (class "Default")
      (node (ref "R30") (pin "2") (pinfunction "2_2") (pintype "unspecified"))
      (node (ref "R31") (pin "1") (pinfunction "1_1") (pintype "unspecified"))
      (node (ref "U32") (pin "7") (pinfunction "CANH_7") (pintype "unspecified"))
      (node (ref "U33") (pin "1") (pinfunction "CAN1-H_1") (pintype "unspecified"))
      (node (ref "U34") (pin "1") (pinfunction "CAN1-H_1") (pintype "unspecified"))
    )
    (net (code "62") (name "Net-(U32-CANL)") (class "Default")
      (node (ref "R30") (pin "1") (pinfunction "1_1") (pintype "unspecified"))
      (node (ref "R32") (pin "2") (pinfunction "2_2") (pintype "unspecified"))
      (node (ref "U32") (pin "6") (pinfunction "CANL_6") (pintype "unspecified"))
      (node (ref "U33") (pin "2") (pinfunction "CAN1-L_2") (pintype "unspecified"))
      (node (ref "U34") (pin "2") (pinfunction "CAN1-L_2") (pintype "unspecified"))
    )
    (net (code "63") (name "POWER+") (class "Default")
      (node (ref "C11") (pin "1") (pinfunction "1_1") (pintype "input"))
      (node (ref "Q1") (pin "5") (pinfunction "D1_5") (pintype "unspecified"))
      (node (ref "Q1") (pin "6") (pinfunction "D1_6") (pintype "unspecified"))
      (node (ref "Q1") (pin "7") (pinfunction "D2_7") (pintype "unspecified"))
      (node (ref "Q1") (pin "8") (pinfunction "D2_8") (pintype "unspecified"))
      (node (ref "SW1") (pin "4") (pinfunction "4_4") (pintype "unspecified"))
      (node (ref "U33") (pin "7") (pinfunction "FU2_1_7") (pintype "unspecified"))
      (node (ref "U33") (pin "8") (pinfunction "FU2_2_8") (pintype "unspecified"))
      (node (ref "U34") (pin "7") (pinfunction "FU1_1_7") (pintype "unspecified"))
      (node (ref "U34") (pin "8") (pinfunction "FU1_2_8") (pintype "unspecified"))
      (node (ref "U7") (pin "1") (pinfunction "VIN_1") (pintype "unspecified"))
    )
    (net (code "64") (name "POWER-") (class "Default")
      (node (ref "C1") (pin "2") (pinfunction "2_2") (pintype "unspecified"))
      (node (ref "C10") (pin "2") (pinfunction "2_2") (pintype "unspecified"))
      (node (ref "C11") (pin "2") (pinfunction "2_2") (pintype "input"))
      (node (ref "C12") (pin "2") (pinfunction "2_2") (pintype "input"))
      (node (ref "C13") (pin "2") (pinfunction "2_2") (pintype "unspecified"))
      (node (ref "C14") (pin "1") (pinfunction "1_1") (pintype "unspecified"))
      (node (ref "C15") (pin "1") (pinfunction "1_1") (pintype "unspecified"))
      (node (ref "C16") (pin "1") (pinfunction "1_1") (pintype "unspecified"))
      (node (ref "C17") (pin "2") (pinfunction "2_2") (pintype "unspecified"))
      (node (ref "C18") (pin "1") (pinfunction "1_1") (pintype "unspecified"))
      (node (ref "C2") (pin "1") (pinfunction "1_1") (pintype "unspecified"))
      (node (ref "C3") (pin "2") (pinfunction "2_2") (pintype "input"))
      (node (ref "C4") (pin "2") (pinfunction "2_2") (pintype "input"))
      (node (ref "C5") (pin "2") (pinfunction "2_2") (pintype "unspecified"))
      (node (ref "C6") (pin "2") (pinfunction "2_2") (pintype "unspecified"))
      (node (ref "C7") (pin "2") (pinfunction "2_2") (pintype "unspecified"))
      (node (ref "C8") (pin "2") (pinfunction "2_2") (pintype "unspecified"))
      (node (ref "C9") (pin "2") (pinfunction "2_2") (pintype "unspecified"))
      (node (ref "D2") (pin "2") (pinfunction "2_2") (pintype "unspecified"))
      (node (ref "D3") (pin "2") (pinfunction "A_2") (pintype "unspecified"))
      (node (ref "J1") (pin "1") (pinfunction "1_1") (pintype "unspecified"))
      (node (ref "J1") (pin "10") (pinfunction "10_10") (pintype "unspecified"))
      (node (ref "J1") (pin "4") (pinfunction "4_4") (pintype "unspecified"))
      (node (ref "J1") (pin "7") (pinfunction "7_7") (pintype "unspecified"))
      (node (ref "J2") (pin "1") (pinfunction "1_1") (pintype "unspecified"))
      (node (ref "J2") (pin "10") (pinfunction "10_10") (pintype "unspecified"))
      (node (ref "J2") (pin "4") (pinfunction "4_4") (pintype "unspecified"))
      (node (ref "J2") (pin "7") (pinfunction "7_7") (pintype "unspecified"))
      (node (ref "J3") (pin "7") (pinfunction "7_7") (pintype "unspecified"))
      (node (ref "R10") (pin "1") (pinfunction "1_1") (pintype "unspecified"))
      (node (ref "R24") (pin "1") (pinfunction "1_1") (pintype "unspecified"))
      (node (ref "R25") (pin "1") (pinfunction "1_1") (pintype "unspecified"))
      (node (ref "R3") (pin "2") (pinfunction "2_2") (pintype "unspecified"))
      (node (ref "R4") (pin "2") (pinfunction "2_2") (pintype "unspecified"))
      (node (ref "SW1") (pin "2") (pinfunction "2_2") (pintype "unspecified"))
      (node (ref "U1") (pin "2") (pinfunction "GND_2") (pintype "unspecified"))
      (node (ref "U12") (pin "3") (pinfunction "GND_3") (pintype "unspecified"))
      (node (ref "U13") (pin "3") (pinfunction "GND_3") (pintype "unspecified"))
      (node (ref "U14") (pin "3") (pinfunction "GND_3") (pintype "unspecified"))
      (node (ref "U17") (pin "3") (pinfunction "GND_3") (pintype "unspecified"))
      (node (ref "U28") (pin "12") (pinfunction "VSSA/VREF-_12") (pintype "unspecified"))
      (node (ref "U28") (pin "18") (pinfunction "VSS_18") (pintype "unspecified"))
      (node (ref "U28") (pin "31") (pinfunction "VSS_31") (pintype "unspecified"))
      (node (ref "U28") (pin "47") (pinfunction "VSS_47") (pintype "unspecified"))
      (node (ref "U28") (pin "63") (pinfunction "VSS_63") (pintype "unspecified"))
      (node (ref "U31") (pin "1") (pinfunction "GND_1") (pintype "bidirectional"))
      (node (ref "U31") (pin "107") (pinfunction "GND_107") (pintype "bidirectional"))
      (node (ref "U31") (pin "108") (pinfunction "GND_108") (pintype "bidirectional"))
      (node (ref "U31") (pin "113") (pinfunction "GND_113") (pintype "bidirectional"))
      (node (ref "U31") (pin "114") (pinfunction "GND_114") (pintype "bidirectional"))
      (node (ref "U31") (pin "119") (pinfunction "GND_119") (pintype "bidirectional"))
      (node (ref "U31") (pin "120") (pinfunction "GND_120") (pintype "bidirectional"))
      (node (ref "U31") (pin "125") (pinfunction "GND_125") (pintype "bidirectional"))
      (node (ref "U31") (pin "126") (pinfunction "GND_126") (pintype "bidirectional"))
      (node (ref "U31") (pin "13") (pinfunction "GND_13") (pintype "bidirectional"))
      (node (ref "U31") (pin "131") (pinfunction "GND_131") (pintype "bidirectional"))
      (node (ref "U31") (pin "132") (pinfunction "GND_132") (pintype "bidirectional"))
      (node (ref "U31") (pin "137") (pinfunction "GND_137") (pintype "bidirectional"))
      (node (ref "U31") (pin "138") (pinfunction "GND_138") (pintype "bidirectional"))
      (node (ref "U31") (pin "14") (pinfunction "GND_14") (pintype "bidirectional"))
      (node (ref "U31") (pin "150") (pinfunction "GND_150") (pintype "bidirectional"))
      (node (ref "U31") (pin "155") (pinfunction "GND_155") (pintype "bidirectional"))
      (node (ref "U31") (pin "156") (pinfunction "GND_156") (pintype "bidirectional"))
      (node (ref "U31") (pin "161") (pinfunction "GND_161") (pintype "bidirectional"))
      (node (ref "U31") (pin "162") (pinfunction "GND_162") (pintype "bidirectional"))
      (node (ref "U31") (pin "167") (pinfunction "GND_167") (pintype "bidirectional"))
      (node (ref "U31") (pin "168") (pinfunction "GND_168") (pintype "bidirectional"))
      (node (ref "U31") (pin "173") (pinfunction "GND_173") (pintype "bidirectional"))
      (node (ref "U31") (pin "174") (pinfunction "GND_174") (pintype "bidirectional"))
      (node (ref "U31") (pin "179") (pinfunction "GND_179") (pintype "bidirectional"))
      (node (ref "U31") (pin "180") (pinfunction "GND_180") (pintype "bidirectional"))
      (node (ref "U31") (pin "185") (pinfunction "GND_185") (pintype "bidirectional"))
      (node (ref "U31") (pin "186") (pinfunction "GND_186") (pintype "bidirectional"))
      (node (ref "U31") (pin "191") (pinfunction "GND_191") (pintype "bidirectional"))
      (node (ref "U31") (pin "192") (pinfunction "GND_192") (pintype "bidirectional"))
      (node (ref "U31") (pin "197") (pinfunction "GND_197") (pintype "bidirectional"))
      (node (ref "U31") (pin "198") (pinfunction "GND_198") (pintype "bidirectional"))
      (node (ref "U31") (pin "2") (pinfunction "GND_2") (pintype "bidirectional"))
      (node (ref "U31") (pin "22") (pinfunction "GND_22") (pintype "bidirectional"))
      (node (ref "U31") (pin "23") (pinfunction "GND_23") (pintype "bidirectional"))
      (node (ref "U31") (pin "32") (pinfunction "GND_32") (pintype "bidirectional"))
      (node (ref "U31") (pin "33") (pinfunction "GND_33") (pintype "bidirectional"))
      (node (ref "U31") (pin "42") (pinfunction "GND_42") (pintype "bidirectional"))
      (node (ref "U31") (pin "43") (pinfunction "GND_43") (pintype "bidirectional"))
      (node (ref "U31") (pin "52") (pinfunction "GND_52") (pintype "bidirectional"))
      (node (ref "U31") (pin "53") (pinfunction "GND_53") (pintype "bidirectional"))
      (node (ref "U31") (pin "59") (pinfunction "GND_59") (pintype "bidirectional"))
      (node (ref "U31") (pin "60") (pinfunction "GND_60") (pintype "bidirectional"))
      (node (ref "U31") (pin "65") (pinfunction "GND_65") (pintype "bidirectional"))
      (node (ref "U31") (pin "66") (pinfunction "GND_66") (pintype "bidirectional"))
      (node (ref "U31") (pin "7") (pinfunction "GND_7") (pintype "bidirectional"))
      (node (ref "U31") (pin "71") (pinfunction "GND_71") (pintype "bidirectional"))
      (node (ref "U31") (pin "74") (pinfunction "GND_74") (pintype "bidirectional"))
      (node (ref "U31") (pin "8") (pinfunction "GND_8") (pintype "bidirectional"))
      (node (ref "U31") (pin "98") (pinfunction "GND_98") (pintype "bidirectional"))
      (node (ref "U32") (pin "2") (pinfunction "GND_2") (pintype "unspecified"))
      (node (ref "U33") (pin "10") (pinfunction "GND_10") (pintype "unspecified"))
      (node (ref "U33") (pin "9") (pinfunction "GND_9") (pintype "unspecified"))
      (node (ref "U34") (pin "10") (pinfunction "GND_10") (pintype "unspecified"))
      (node (ref "U34") (pin "9") (pinfunction "GND_9") (pintype "unspecified"))
      (node (ref "U4") (pin "5") (pinfunction "GND_5") (pintype "unspecified"))
      (node (ref "U4") (pin "6") (pinfunction "EP_6") (pintype "unspecified"))
      (node (ref "U4") (pin "7") (pinfunction "EP_7") (pintype "unspecified"))
      (node (ref "U6") (pin "4") (pinfunction "GND_4") (pintype "unspecified"))
      (node (ref "U6") (pin "9") (pinfunction "EP_9") (pintype "unspecified"))
      (node (ref "U7") (pin "3") (pinfunction "GND_3") (pintype "unspecified"))
      (node (ref "U7") (pin "5") (pinfunction "ON/OFF_5") (pintype "unspecified"))
      (node (ref "U7") (pin "6") (pinfunction "GND_6") (pintype "unspecified"))
      (node (ref "U8") (pin "3") (pinfunction "GND_3") (pintype "unspecified"))
      (node (ref "U8") (pin "5") (pinfunction "ON/OFF_5") (pintype "unspecified"))
      (node (ref "U8") (pin "6") (pinfunction "GND_6") (pintype "unspecified"))
    )
    (net (code "65") (name "unconnected-(J1-Pad12)") (class "Default")
      (node (ref "J1") (pin "12") (pinfunction "12_12") (pintype "unspecified"))
    )
    (net (code "66") (name "unconnected-(J1-PadG1)") (class "Default")
      (node (ref "J1") (pin "G1") (pinfunction "G1_G1") (pintype "unspecified"))
    )
    (net (code "67") (name "unconnected-(J1-PadG2)") (class "Default")
      (node (ref "J1") (pin "G2") (pinfunction "G2_G2") (pintype "unspecified"))
    )
    (net (code "68") (name "unconnected-(J2-Pad12)") (class "Default")
      (node (ref "J2") (pin "12") (pinfunction "12_12") (pintype "unspecified"))
    )
    (net (code "69") (name "unconnected-(J2-PadG1)") (class "Default")
      (node (ref "J2") (pin "G1") (pinfunction "G1_G1") (pintype "unspecified"))
    )
    (net (code "70") (name "unconnected-(J2-PadG2)") (class "Default")
      (node (ref "J2") (pin "G2") (pinfunction "G2_G2") (pintype "unspecified"))
    )
    (net (code "71") (name "unconnected-(U1-ADD1-Pad3)") (class "Default")
      (node (ref "U1") (pin "3") (pinfunction "ADD1_3") (pintype "unspecified+no_connect"))
    )
    (net (code "72") (name "unconnected-(U4-D+-Pad3)") (class "Default")
      (node (ref "U4") (pin "3") (pinfunction "D+_3") (pintype "unspecified"))
    )
    (net (code "73") (name "unconnected-(U4-D--Pad2)") (class "Default")
      (node (ref "U4") (pin "2") (pinfunction "D-_2") (pintype "unspecified"))
    )
    (net (code "74") (name "unconnected-(U4-ID-Pad4)") (class "Default")
      (node (ref "U4") (pin "4") (pinfunction "ID_4") (pintype "unspecified+no_connect"))
    )
    (net (code "75") (name "unconnected-(U12-NC-Pad1)") (class "Default")
      (node (ref "U12") (pin "1") (pinfunction "NC_1") (pintype "unspecified+no_connect"))
    )
    (net (code "76") (name "unconnected-(U13-NC-Pad1)") (class "Default")
      (node (ref "U13") (pin "1") (pinfunction "NC_1") (pintype "unspecified+no_connect"))
    )
    (net (code "77") (name "unconnected-(U17-NC-Pad1)") (class "Default")
      (node (ref "U17") (pin "1") (pinfunction "NC_1") (pintype "unspecified+no_connect"))
    )
    (net (code "78") (name "unconnected-(U28-PA0-Pad14)") (class "Default")
      (node (ref "U28") (pin "14") (pinfunction "PA0_14") (pintype "unspecified"))
    )
    (net (code "79") (name "unconnected-(U28-PA1-Pad15)") (class "Default")
      (node (ref "U28") (pin "15") (pinfunction "PA1_15") (pintype "unspecified"))
    )
    (net (code "80") (name "unconnected-(U28-PA4-Pad20)") (class "Default")
      (node (ref "U28") (pin "20") (pinfunction "PA4_20") (pintype "unspecified"))
    )
    (net (code "81") (name "unconnected-(U28-PA13-Pad46)") (class "Default")
      (node (ref "U28") (pin "46") (pinfunction "PA13_46") (pintype "unspecified"))
    )
    (net (code "82") (name "unconnected-(U28-PA14-Pad49)") (class "Default")
      (node (ref "U28") (pin "49") (pinfunction "PA14_49") (pintype "unspecified"))
    )
    (net (code "83") (name "unconnected-(U28-PB3-Pad55)") (class "Default")
      (node (ref "U28") (pin "55") (pinfunction "PB3_55") (pintype "unspecified"))
    )
    (net (code "84") (name "unconnected-(U28-PB4-Pad56)") (class "Default")
      (node (ref "U28") (pin "56") (pinfunction "PB4_56") (pintype "unspecified"))
    )
    (net (code "85") (name "unconnected-(U28-PB8-Pad61)") (class "Default")
      (node (ref "U28") (pin "61") (pinfunction "PB8_61") (pintype "unspecified"))
    )
    (net (code "86") (name "unconnected-(U28-PB9-Pad62)") (class "Default")
      (node (ref "U28") (pin "62") (pinfunction "PB9_62") (pintype "unspecified"))
    )
    (net (code "87") (name "unconnected-(U28-PB12-Pad33)") (class "Default")
      (node (ref "U28") (pin "33") (pinfunction "PB12_33") (pintype "unspecified"))
    )
    (net (code "88") (name "unconnected-(U28-PB13-Pad34)") (class "Default")
      (node (ref "U28") (pin "34") (pinfunction "PB13_34") (pintype "unspecified"))
    )
    (net (code "89") (name "unconnected-(U28-PB14-Pad35)") (class "Default")
      (node (ref "U28") (pin "35") (pinfunction "PB14_35") (pintype "unspecified"))
    )
    (net (code "90") (name "unconnected-(U28-PB15-Pad36)") (class "Default")
      (node (ref "U28") (pin "36") (pinfunction "PB15_36") (pintype "unspecified"))
    )
    (net (code "91") (name "unconnected-(U28-PC0-Pad8)") (class "Default")
      (node (ref "U28") (pin "8") (pinfunction "PC0_8") (pintype "unspecified"))
    )
    (net (code "92") (name "unconnected-(U28-PC1-Pad9)") (class "Default")
      (node (ref "U28") (pin "9") (pinfunction "PC1_9") (pintype "unspecified"))
    )
    (net (code "93") (name "unconnected-(U28-PC2-Pad10)") (class "Default")
      (node (ref "U28") (pin "10") (pinfunction "PC2_10") (pintype "unspecified"))
    )
    (net (code "94") (name "unconnected-(U28-PC3-Pad11)") (class "Default")
      (node (ref "U28") (pin "11") (pinfunction "PC3_11") (pintype "unspecified"))
    )
    (net (code "95") (name "unconnected-(U28-PC6-Pad37)") (class "Default")
      (node (ref "U28") (pin "37") (pinfunction "PC6_37") (pintype "unspecified"))
    )
    (net (code "96") (name "unconnected-(U28-PC7-Pad38)") (class "Default")
      (node (ref "U28") (pin "38") (pinfunction "PC7_38") (pintype "unspecified"))
    )
    (net (code "97") (name "unconnected-(U28-PC8-Pad39)") (class "Default")
      (node (ref "U28") (pin "39") (pinfunction "PC8_39") (pintype "unspecified"))
    )
    (net (code "98") (name "unconnected-(U28-PC9-Pad40)") (class "Default")
      (node (ref "U28") (pin "40") (pinfunction "PC9_40") (pintype "unspecified"))
    )
    (net (code "99") (name "unconnected-(U28-PC10-Pad51)") (class "Default")
      (node (ref "U28") (pin "51") (pinfunction "PC10_51") (pintype "unspecified"))
    )
    (net (code "100") (name "unconnected-(U28-PC11-Pad52)") (class "Default")
      (node (ref "U28") (pin "52") (pinfunction "PC11_52") (pintype "unspecified"))
    )
    (net (code "101") (name "unconnected-(U28-PC12-Pad53)") (class "Default")
      (node (ref "U28") (pin "53") (pinfunction "PC12_53") (pintype "unspecified"))
    )
    (net (code "102") (name "unconnected-(U28-PC13-Pad2)") (class "Default")
      (node (ref "U28") (pin "2") (pinfunction "PC13_2") (pintype "unspecified"))
    )
    (net (code "103") (name "unconnected-(U28-PC14{slash}OSC32_IN-Pad3)") (class "Default")
      (node (ref "U28") (pin "3") (pinfunction "PC14/OSC32_IN_3") (pintype "unspecified"))
    )
    (net (code "104") (name "unconnected-(U28-PC15{slash}OSC32_OUT-Pad4)") (class "Default")
      (node (ref "U28") (pin "4") (pinfunction "PC15/OSC32_OUT_4") (pintype "unspecified"))
    )
    (net (code "105") (name "unconnected-(U28-PD2-Pad54)") (class "Default")
      (node (ref "U28") (pin "54") (pinfunction "PD2_54") (pintype "unspecified"))
    )
    (net (code "106") (name "unconnected-(U28-PH0{slash}OSCIN-Pad5)") (class "Default")
      (node (ref "U28") (pin "5") (pinfunction "PH0/OSCIN_5") (pintype "unspecified"))
    )
    (net (code "107") (name "unconnected-(U28-PH1{slash}OSCOUT-Pad6)") (class "Default")
      (node (ref "U28") (pin "6") (pinfunction "PH1/OSCOUT_6") (pintype "unspecified"))
    )
    (net (code "108") (name "unconnected-(U28-PH3-BOOT0-Pad60)") (class "Default")
      (node (ref "U28") (pin "60") (pinfunction "PH3-BOOT0_60") (pintype "unspecified"))
    )
    (net (code "109") (name "unconnected-(U31-AnalogIP0-Pad96)") (class "Default")
      (node (ref "U31") (pin "96") (pinfunction "AnalogIP0_96") (pintype "bidirectional"))
    )
    (net (code "110") (name "unconnected-(U31-AnalogIP1-Pad94)") (class "Default")
      (node (ref "U31") (pin "94") (pinfunction "AnalogIP1_94") (pintype "bidirectional"))
    )
    (net (code "111") (name "unconnected-(U31-BT_nDisable-Pad91)") (class "Default")
      (node (ref "U31") (pin "91") (pinfunction "BT_nDisable_91") (pintype "bidirectional"))
    )
    (net (code "112") (name "unconnected-(U31-CAM1_D2_N-Pad133)") (class "Default")
      (node (ref "U31") (pin "133") (pinfunction "CAM1_D2_N_133") (pintype "bidirectional"))
    )
    (net (code "113") (name "unconnected-(U31-CAM1_D2_P-Pad135)") (class "Default")
      (node (ref "U31") (pin "135") (pinfunction "CAM1_D2_P_135") (pintype "bidirectional"))
    )
    (net (code "114") (name "unconnected-(U31-CAM1_D3_N-Pad139)") (class "Default")
      (node (ref "U31") (pin "139") (pinfunction "CAM1_D3_N_139") (pintype "bidirectional"))
    )
    (net (code "115") (name "unconnected-(U31-CAM1_D3_P-Pad141)") (class "Default")
      (node (ref "U31") (pin "141") (pinfunction "CAM1_D3_P_141") (pintype "bidirectional"))
    )
    (net (code "116") (name "unconnected-(U31-CM4_1.8V-Pad88)") (class "Default")
      (node (ref "U31") (pin "88") (pinfunction "CM4_1.8V_88") (pintype "bidirectional"))
    )
    (net (code "117") (name "unconnected-(U31-CM4_1.8V-Pad90)") (class "Default")
      (node (ref "U31") (pin "90") (pinfunction "CM4_1.8V_90") (pintype "bidirectional"))
    )
    (net (code "118") (name "unconnected-(U31-DSI0_C_N-Pad169)") (class "Default")
      (node (ref "U31") (pin "169") (pinfunction "DSI0_C_N_169") (pintype "bidirectional"))
    )
    (net (code "119") (name "unconnected-(U31-DSI0_C_P-Pad171)") (class "Default")
      (node (ref "U31") (pin "171") (pinfunction "DSI0_C_P_171") (pintype "bidirectional"))
    )
    (net (code "120") (name "unconnected-(U31-DSI0_D0_N-Pad157)") (class "Default")
      (node (ref "U31") (pin "157") (pinfunction "DSI0_D0_N_157") (pintype "bidirectional"))
    )
    (net (code "121") (name "unconnected-(U31-DSI0_D0_P-Pad159)") (class "Default")
      (node (ref "U31") (pin "159") (pinfunction "DSI0_D0_P_159") (pintype "bidirectional"))
    )
    (net (code "122") (name "unconnected-(U31-DSI0_D1_N-Pad163)") (class "Default")
      (node (ref "U31") (pin "163") (pinfunction "DSI0_D1_N_163") (pintype "bidirectional"))
    )
    (net (code "123") (name "unconnected-(U31-DSI0_D1_P-Pad165)") (class "Default")
      (node (ref "U31") (pin "165") (pinfunction "DSI0_D1_P_165") (pintype "bidirectional"))
    )
    (net (code "124") (name "unconnected-(U31-DSI1_C_N-Pad187)") (class "Default")
      (node (ref "U31") (pin "187") (pinfunction "DSI1_C_N_187") (pintype "bidirectional"))
    )
    (net (code "125") (name "unconnected-(U31-DSI1_C_P-Pad189)") (class "Default")
      (node (ref "U31") (pin "189") (pinfunction "DSI1_C_P_189") (pintype "bidirectional"))
    )
    (net (code "126") (name "unconnected-(U31-DSI1_D0_N-Pad175)") (class "Default")
      (node (ref "U31") (pin "175") (pinfunction "DSI1_D0_N_175") (pintype "bidirectional"))
    )
    (net (code "127") (name "unconnected-(U31-DSI1_D0_P-Pad177)") (class "Default")
      (node (ref "U31") (pin "177") (pinfunction "DSI1_D0_P_177") (pintype "bidirectional"))
    )
    (net (code "128") (name "unconnected-(U31-DSI1_D1_N-Pad181)") (class "Default")
      (node (ref "U31") (pin "181") (pinfunction "DSI1_D1_N_181") (pintype "bidirectional"))
    )
    (net (code "129") (name "unconnected-(U31-DSI1_D1_P-Pad183)") (class "Default")
      (node (ref "U31") (pin "183") (pinfunction "DSI1_D1_P_183") (pintype "bidirectional"))
    )
    (net (code "130") (name "unconnected-(U31-DSI1_D2_N-Pad193)") (class "Default")
      (node (ref "U31") (pin "193") (pinfunction "DSI1_D2_N_193") (pintype "bidirectional"))
    )
    (net (code "131") (name "unconnected-(U31-DSI1_D2_P-Pad195)") (class "Default")
      (node (ref "U31") (pin "195") (pinfunction "DSI1_D2_P_195") (pintype "bidirectional"))
    )
    (net (code "132") (name "unconnected-(U31-DSI_D3_N-Pad194)") (class "Default")
      (node (ref "U31") (pin "194") (pinfunction "DSI_D3_N_194") (pintype "bidirectional"))
    )
    (net (code "133") (name "unconnected-(U31-DSI_D3_P-Pad196)") (class "Default")
      (node (ref "U31") (pin "196") (pinfunction "DSI_D3_P_196") (pintype "bidirectional"))
    )
    (net (code "134") (name "unconnected-(U31-EEPROM_nWP-Pad20)") (class "Default")
      (node (ref "U31") (pin "20") (pinfunction "EEPROM_nWP_20") (pintype "bidirectional"))
    )
    (net (code "135") (name "unconnected-(U31-ETH_D0_N-Pad10)") (class "Default")
      (node (ref "U31") (pin "10") (pinfunction "ETH_D0_N_10") (pintype "bidirectional"))
    )
    (net (code "136") (name "unconnected-(U31-ETH_D0_P-Pad12)") (class "Default")
      (node (ref "U31") (pin "12") (pinfunction "ETH_D0_P_12") (pintype "bidirectional"))
    )
    (net (code "137") (name "unconnected-(U31-ETH_D1_N-Pad6)") (class "Default")
      (node (ref "U31") (pin "6") (pinfunction "ETH_D1_N_6") (pintype "bidirectional"))
    )
    (net (code "138") (name "unconnected-(U31-ETH_D1_P-Pad4)") (class "Default")
      (node (ref "U31") (pin "4") (pinfunction "ETH_D1_P_4") (pintype "bidirectional"))
    )
    (net (code "139") (name "unconnected-(U31-ETH_D2_N-Pad9)") (class "Default")
      (node (ref "U31") (pin "9") (pinfunction "ETH_D2_N_9") (pintype "bidirectional"))
    )
    (net (code "140") (name "unconnected-(U31-ETH_D2_P-Pad11)") (class "Default")
      (node (ref "U31") (pin "11") (pinfunction "ETH_D2_P_11") (pintype "bidirectional"))
    )
    (net (code "141") (name "unconnected-(U31-ETH_D3_N-Pad5)") (class "Default")
      (node (ref "U31") (pin "5") (pinfunction "ETH_D3_N_5") (pintype "bidirectional"))
    )
    (net (code "142") (name "unconnected-(U31-ETH_D3_P-Pad3)") (class "Default")
      (node (ref "U31") (pin "3") (pinfunction "ETH_D3_P_3") (pintype "bidirectional"))
    )
    (net (code "143") (name "unconnected-(U31-ETH_SYNC_IN-Pad16)") (class "Default")
      (node (ref "U31") (pin "16") (pinfunction "ETH_SYNC_IN_16") (pintype "bidirectional"))
    )
    (net (code "144") (name "unconnected-(U31-ETH_SYNC_OUT-Pad18)") (class "Default")
      (node (ref "U31") (pin "18") (pinfunction "ETH_SYNC_OUT_18") (pintype "bidirectional"))
    )
    (net (code "145") (name "unconnected-(U31-ETH_nLED1-Pad19)") (class "Default")
      (node (ref "U31") (pin "19") (pinfunction "ETH_nLED1_19") (pintype "bidirectional"))
    )
    (net (code "146") (name "unconnected-(U31-ETH_nLED2-Pad17)") (class "Default")
      (node (ref "U31") (pin "17") (pinfunction "ETH_nLED2_17") (pintype "bidirectional"))
    )
    (net (code "147") (name "unconnected-(U31-ETH_nLED3-Pad15)") (class "Default")
      (node (ref "U31") (pin "15") (pinfunction "ETH_nLED3_15") (pintype "bidirectional"))
    )
    (net (code "148") (name "unconnected-(U31-GLOBAL_EN-Pad99)") (class "Default")
      (node (ref "U31") (pin "99") (pinfunction "GLOBAL_EN_99") (pintype "bidirectional"))
    )
    (net (code "149") (name "unconnected-(U31-GND-Pad144)") (class "Default")
      (node (ref "U31") (pin "144") (pinfunction "GND_144") (pintype "bidirectional"))
    )
    (net (code "150") (name "unconnected-(U31-GPIO2-Pad58)") (class "Default")
      (node (ref "U31") (pin "58") (pinfunction "GPIO2_58") (pintype "bidirectional"))
    )
    (net (code "151") (name "unconnected-(U31-GPIO4-Pad54)") (class "Default")
      (node (ref "U31") (pin "54") (pinfunction "GPIO4_54") (pintype "bidirectional"))
    )
    (net (code "152") (name "unconnected-(U31-GPIO5-Pad34)") (class "Default")
      (node (ref "U31") (pin "34") (pinfunction "GPIO5_34") (pintype "bidirectional"))
    )
    (net (code "153") (name "unconnected-(U31-GPIO6-Pad30)") (class "Default")
      (node (ref "U31") (pin "30") (pinfunction "GPIO6_30") (pintype "bidirectional"))
    )
    (net (code "154") (name "unconnected-(U31-GPIO7-Pad37)") (class "Default")
      (node (ref "U31") (pin "37") (pinfunction "GPIO7_37") (pintype "bidirectional"))
    )
    (net (code "155") (name "unconnected-(U31-GPIO8-Pad39)") (class "Default")
      (node (ref "U31") (pin "39") (pinfunction "GPIO8_39") (pintype "bidirectional"))
    )
    (net (code "156") (name "unconnected-(U31-GPIO9-Pad40)") (class "Default")
      (node (ref "U31") (pin "40") (pinfunction "GPIO9_40") (pintype "bidirectional"))
    )
    (net (code "157") (name "unconnected-(U31-GPIO10-Pad44)") (class "Default")
      (node (ref "U31") (pin "44") (pinfunction "GPIO10_44") (pintype "bidirectional"))
    )
    (net (code "158") (name "unconnected-(U31-GPIO11-Pad38)") (class "Default")
      (node (ref "U31") (pin "38") (pinfunction "GPIO11_38") (pintype "bidirectional"))
    )
    (net (code "159") (name "unconnected-(U31-GPIO12-Pad31)") (class "Default")
      (node (ref "U31") (pin "31") (pinfunction "GPIO12_31") (pintype "bidirectional"))
    )
    (net (code "160") (name "unconnected-(U31-GPIO13-Pad28)") (class "Default")
      (node (ref "U31") (pin "28") (pinfunction "GPIO13_28") (pintype "bidirectional"))
    )
    (net (code "161") (name "unconnected-(U31-GPIO16-Pad29)") (class "Default")
      (node (ref "U31") (pin "29") (pinfunction "GPIO16_29") (pintype "bidirectional"))
    )
    (net (code "162") (name "unconnected-(U31-GPIO17-Pad50)") (class "Default")
      (node (ref "U31") (pin "50") (pinfunction "GPIO17_50") (pintype "bidirectional"))
    )
    (net (code "163") (name "unconnected-(U31-GPIO18-Pad49)") (class "Default")
      (node (ref "U31") (pin "49") (pinfunction "GPIO18_49") (pintype "bidirectional"))
    )
    (net (code "164") (name "unconnected-(U31-GPIO19-Pad26)") (class "Default")
      (node (ref "U31") (pin "26") (pinfunction "GPIO19_26") (pintype "bidirectional"))
    )
    (net (code "165") (name "unconnected-(U31-GPIO20-Pad27)") (class "Default")
      (node (ref "U31") (pin "27") (pinfunction "GPIO20_27") (pintype "bidirectional"))
    )
    (net (code "166") (name "unconnected-(U31-GPIO21-Pad25)") (class "Default")
      (node (ref "U31") (pin "25") (pinfunction "GPIO21_25") (pintype "bidirectional"))
    )
    (net (code "167") (name "unconnected-(U31-GPIO22-Pad46)") (class "Default")
      (node (ref "U31") (pin "46") (pinfunction "GPIO22_46") (pintype "bidirectional"))
    )
    (net (code "168") (name "unconnected-(U31-GPIO23-Pad47)") (class "Default")
      (node (ref "U31") (pin "47") (pinfunction "GPIO23_47") (pintype "bidirectional"))
    )
    (net (code "169") (name "unconnected-(U31-GPIO24-Pad45)") (class "Default")
      (node (ref "U31") (pin "45") (pinfunction "GPIO24_45") (pintype "bidirectional"))
    )
    (net (code "170") (name "unconnected-(U31-GPIO25-Pad41)") (class "Default")
      (node (ref "U31") (pin "41") (pinfunction "GPIO25_41") (pintype "bidirectional"))
    )
    (net (code "171") (name "unconnected-(U31-GPIO26-Pad24)") (class "Default")
      (node (ref "U31") (pin "24") (pinfunction "GPIO26_24") (pintype "bidirectional"))
    )
    (net (code "172") (name "unconnected-(U31-GPIO27-Pad48)") (class "Default")
      (node (ref "U31") (pin "48") (pinfunction "GPIO27_48") (pintype "bidirectional"))
    )
    (net (code "173") (name "unconnected-(U31-HDMI0_CEC-Pad151)") (class "Default")
      (node (ref "U31") (pin "151") (pinfunction "HDMI0_CEC_151") (pintype "bidirectional"))
    )
    (net (code "174") (name "unconnected-(U31-HDMI0_CLK_N-Pad190)") (class "Default")
      (node (ref "U31") (pin "190") (pinfunction "HDMI0_CLK_N_190") (pintype "bidirectional"))
    )
    (net (code "175") (name "unconnected-(U31-HDMI0_CLK_P-Pad188)") (class "Default")
      (node (ref "U31") (pin "188") (pinfunction "HDMI0_CLK_P_188") (pintype "bidirectional"))
    )
    (net (code "176") (name "unconnected-(U31-HDMI0_HPD-Pad153)") (class "Default")
      (node (ref "U31") (pin "153") (pinfunction "HDMI0_HPD_153") (pintype "bidirectional"))
    )
    (net (code "177") (name "unconnected-(U31-HDMI0_SCL-Pad200)") (class "Default")
      (node (ref "U31") (pin "200") (pinfunction "HDMI0_SCL_200") (pintype "bidirectional"))
    )
    (net (code "178") (name "unconnected-(U31-HDMI0_SDA-Pad199)") (class "Default")
      (node (ref "U31") (pin "199") (pinfunction "HDMI0_SDA_199") (pintype "bidirectional"))
    )
    (net (code "179") (name "unconnected-(U31-HDMI0_TX0_N-Pad184)") (class "Default")
      (node (ref "U31") (pin "184") (pinfunction "HDMI0_TX0_N_184") (pintype "bidirectional"))
    )
    (net (code "180") (name "unconnected-(U31-HDMI0_TX0_P-Pad182)") (class "Default")
      (node (ref "U31") (pin "182") (pinfunction "HDMI0_TX0_P_182") (pintype "bidirectional"))
    )
    (net (code "181") (name "unconnected-(U31-HDMI0_TX1_N-Pad178)") (class "Default")
      (node (ref "U31") (pin "178") (pinfunction "HDMI0_TX1_N_178") (pintype "bidirectional"))
    )
    (net (code "182") (name "unconnected-(U31-HDMI0_TX1_P-Pad176)") (class "Default")
      (node (ref "U31") (pin "176") (pinfunction "HDMI0_TX1_P_176") (pintype "bidirectional"))
    )
    (net (code "183") (name "unconnected-(U31-HDMI0_TX2_N-Pad172)") (class "Default")
      (node (ref "U31") (pin "172") (pinfunction "HDMI0_TX2_N_172") (pintype "bidirectional"))
    )
    (net (code "184") (name "unconnected-(U31-HDMI0_TX2_P-Pad170)") (class "Default")
      (node (ref "U31") (pin "170") (pinfunction "HDMI0_TX2_P_170") (pintype "bidirectional"))
    )
    (net (code "185") (name "unconnected-(U31-HDMI1_CEC-Pad149)") (class "Default")
      (node (ref "U31") (pin "149") (pinfunction "HDMI1_CEC_149") (pintype "bidirectional"))
    )
    (net (code "186") (name "unconnected-(U31-HDMI1_CLK_N-Pad166)") (class "Default")
      (node (ref "U31") (pin "166") (pinfunction "HDMI1_CLK_N_166") (pintype "bidirectional"))
    )
    (net (code "187") (name "unconnected-(U31-HDMI1_CLK_P-Pad164)") (class "Default")
      (node (ref "U31") (pin "164") (pinfunction "HDMI1_CLK_P_164") (pintype "bidirectional"))
    )
    (net (code "188") (name "unconnected-(U31-HDMI1_HPD-Pad143)") (class "Default")
      (node (ref "U31") (pin "143") (pinfunction "HDMI1_HPD_143") (pintype "bidirectional"))
    )
    (net (code "189") (name "unconnected-(U31-HDMI1_SCL-Pad147)") (class "Default")
      (node (ref "U31") (pin "147") (pinfunction "HDMI1_SCL_147") (pintype "bidirectional"))
    )
    (net (code "190") (name "unconnected-(U31-HDMI1_SDA-Pad145)") (class "Default")
      (node (ref "U31") (pin "145") (pinfunction "HDMI1_SDA_145") (pintype "bidirectional"))
    )
    (net (code "191") (name "unconnected-(U31-HDMI1_TX0_N-Pad160)") (class "Default")
      (node (ref "U31") (pin "160") (pinfunction "HDMI1_TX0_N_160") (pintype "bidirectional"))
    )
    (net (code "192") (name "unconnected-(U31-HDMI1_TX0_P-Pad158)") (class "Default")
      (node (ref "U31") (pin "158") (pinfunction "HDMI1_TX0_P_158") (pintype "bidirectional"))
    )
    (net (code "193") (name "unconnected-(U31-HDMI1_TX1_N-Pad154)") (class "Default")
      (node (ref "U31") (pin "154") (pinfunction "HDMI1_TX1_N_154") (pintype "bidirectional"))
    )
    (net (code "194") (name "unconnected-(U31-HDMI1_TX1_P-Pad152)") (class "Default")
      (node (ref "U31") (pin "152") (pinfunction "HDMI1_TX1_P_152") (pintype "bidirectional"))
    )
    (net (code "195") (name "unconnected-(U31-HDMI1_TX2_N-Pad148)") (class "Default")
      (node (ref "U31") (pin "148") (pinfunction "HDMI1_TX2_N_148") (pintype "bidirectional"))
    )
    (net (code "196") (name "unconnected-(U31-HDMI1_TX2_P-Pad146)") (class "Default")
      (node (ref "U31") (pin "146") (pinfunction "HDMI1_TX2_P_146") (pintype "bidirectional"))
    )
    (net (code "197") (name "unconnected-(U31-PCIe_CLK_N-Pad112)") (class "Default")
      (node (ref "U31") (pin "112") (pinfunction "PCIe_CLK_N_112") (pintype "bidirectional"))
    )
    (net (code "198") (name "unconnected-(U31-PCIe_CLK_P-Pad110)") (class "Default")
      (node (ref "U31") (pin "110") (pinfunction "PCIe_CLK_P_110") (pintype "bidirectional"))
    )
    (net (code "199") (name "unconnected-(U31-PCIe_CLK_nREQ-Pad102)") (class "Default")
      (node (ref "U31") (pin "102") (pinfunction "PCIe_CLK_nREQ_102") (pintype "bidirectional"))
    )
    (net (code "200") (name "unconnected-(U31-PCIe_RX_N-Pad118)") (class "Default")
      (node (ref "U31") (pin "118") (pinfunction "PCIe_RX_N_118") (pintype "bidirectional"))
    )
    (net (code "201") (name "unconnected-(U31-PCIe_RX_P-Pad116)") (class "Default")
      (node (ref "U31") (pin "116") (pinfunction "PCIe_RX_P_116") (pintype "bidirectional"))
    )
    (net (code "202") (name "unconnected-(U31-PCIe_TX_N-Pad124)") (class "Default")
      (node (ref "U31") (pin "124") (pinfunction "PCIe_TX_N_124") (pintype "bidirectional"))
    )
    (net (code "203") (name "unconnected-(U31-PCIe_TX_P-Pad122)") (class "Default")
      (node (ref "U31") (pin "122") (pinfunction "PCIe_TX_P_122") (pintype "bidirectional"))
    )
    (net (code "204") (name "unconnected-(U31-PCIe_nRST-Pad109)") (class "Default")
      (node (ref "U31") (pin "109") (pinfunction "PCIe_nRST_109") (pintype "bidirectional"))
    )
    (net (code "205") (name "unconnected-(U31-PI_nLED_ACTIVITY-Pad21)") (class "Default")
      (node (ref "U31") (pin "21") (pinfunction "PI_nLED_ACTIVITY_21") (pintype "bidirectional"))
    )
    (net (code "206") (name "unconnected-(U31-Pi_LED_nPWR-Pad95)") (class "Default")
      (node (ref "U31") (pin "95") (pinfunction "Pi_LED_nPWR_95") (pintype "bidirectional"))
    )
    (net (code "207") (name "unconnected-(U31-RESERVED-Pad76)") (class "Default")
      (node (ref "U31") (pin "76") (pinfunction "RESERVED_76") (pintype "bidirectional"))
    )
    (net (code "208") (name "unconnected-(U31-RESERVED-Pad104)") (class "Default")
      (node (ref "U31") (pin "104") (pinfunction "RESERVED_104") (pintype "bidirectional"))
    )
    (net (code "209") (name "unconnected-(U31-RESERVED-Pad106)") (class "Default")
      (node (ref "U31") (pin "106") (pinfunction "RESERVED_106") (pintype "bidirectional"))
    )
    (net (code "210") (name "unconnected-(U31-RUN_PG-Pad92)") (class "Default")
      (node (ref "U31") (pin "92") (pinfunction "RUN_PG_92") (pintype "bidirectional"))
    )
    (net (code "211") (name "unconnected-(U31-SD_CLK-Pad57)") (class "Default")
      (node (ref "U31") (pin "57") (pinfunction "SD_CLK_57") (pintype "bidirectional"))
    )
    (net (code "212") (name "unconnected-(U31-SD_CMD-Pad62)") (class "Default")
      (node (ref "U31") (pin "62") (pinfunction "SD_CMD_62") (pintype "bidirectional"))
    )
    (net (code "213") (name "unconnected-(U31-SD_DAT0-Pad63)") (class "Default")
      (node (ref "U31") (pin "63") (pinfunction "SD_DAT0_63") (pintype "bidirectional"))
    )
    (net (code "214") (name "unconnected-(U31-SD_DAT1-Pad67)") (class "Default")
      (node (ref "U31") (pin "67") (pinfunction "SD_DAT1_67") (pintype "bidirectional"))
    )
    (net (code "215") (name "unconnected-(U31-SD_DAT2-Pad69)") (class "Default")
      (node (ref "U31") (pin "69") (pinfunction "SD_DAT2_69") (pintype "bidirectional"))
    )
    (net (code "216") (name "unconnected-(U31-SD_DAT3-Pad61)") (class "Default")
      (node (ref "U31") (pin "61") (pinfunction "SD_DAT3_61") (pintype "bidirectional"))
    )
    (net (code "217") (name "unconnected-(U31-SD_DAT4-Pad68)") (class "Default")
      (node (ref "U31") (pin "68") (pinfunction "SD_DAT4_68") (pintype "bidirectional"))
    )
    (net (code "218") (name "unconnected-(U31-SD_DAT5-Pad64)") (class "Default")
      (node (ref "U31") (pin "64") (pinfunction "SD_DAT5_64") (pintype "bidirectional"))
    )
    (net (code "219") (name "unconnected-(U31-SD_DAT6-Pad72)") (class "Default")
      (node (ref "U31") (pin "72") (pinfunction "SD_DAT6_72") (pintype "bidirectional"))
    )
    (net (code "220") (name "unconnected-(U31-SD_DAT7-Pad70)") (class "Default")
      (node (ref "U31") (pin "70") (pinfunction "SD_DAT7_70") (pintype "bidirectional"))
    )
    (net (code "221") (name "unconnected-(U31-SD_PWR_ON-Pad75)") (class "Default")
      (node (ref "U31") (pin "75") (pinfunction "SD_PWR_ON_75") (pintype "bidirectional"))
    )
    (net (code "222") (name "unconnected-(U31-SD_VDD_OVERIDE-Pad73)") (class "Default")
      (node (ref "U31") (pin "73") (pinfunction "SD_VDD_OVERIDE_73") (pintype "bidirectional"))
    )
    (net (code "223") (name "unconnected-(U31-USB_N-Pad103)") (class "Default")
      (node (ref "U31") (pin "103") (pinfunction "USB_N_103") (pintype "bidirectional"))
    )
    (net (code "224") (name "unconnected-(U31-USB_OTG_ID-Pad101)") (class "Default")
      (node (ref "U31") (pin "101") (pinfunction "USB_OTG_ID_101") (pintype "bidirectional"))
    )
    (net (code "225") (name "unconnected-(U31-USB_P-Pad105)") (class "Default")
      (node (ref "U31") (pin "105") (pinfunction "USB_P_105") (pintype "bidirectional"))
    )
    (net (code "226") (name "unconnected-(U31-VDAC_COMP-Pad111)") (class "Default")
      (node (ref "U31") (pin "111") (pinfunction "VDAC_COMP_111") (pintype "bidirectional"))
    )
    (net (code "227") (name "unconnected-(U31-nEXTRST-Pad100)") (class "Default")
      (node (ref "U31") (pin "100") (pinfunction "nEXTRST_100") (pintype "bidirectional"))
    )
    (net (code "228") (name "unconnected-(U31-nRPIBOOT-Pad93)") (class "Default")
      (node (ref "U31") (pin "93") (pinfunction "nRPIBOOT_93") (pintype "bidirectional"))
    )
    (net (code "229") (name "unconnected-(U33-CAN2-H-Pad3)") (class "Default")
      (node (ref "U33") (pin "3") (pinfunction "CAN2-H_3") (pintype "unspecified"))
    )
    (net (code "230") (name "unconnected-(U33-CAN2-L-Pad4)") (class "Default")
      (node (ref "U33") (pin "4") (pinfunction "CAN2-L_4") (pintype "unspecified"))
    )
    (net (code "231") (name "unconnected-(U34-CAN2-H-Pad3)") (class "Default")
      (node (ref "U34") (pin "3") (pinfunction "CAN2-H_3") (pintype "unspecified"))
    )
    (net (code "232") (name "unconnected-(U34-CAN2-L-Pad4)") (class "Default")
      (node (ref "U34") (pin "4") (pinfunction "CAN2-L_4") (pintype "unspecified"))
    )
  )
)
